# Balancing_Robot_1_2_Main.net
KiCad netlist of a schematic drawn in Altium Designer
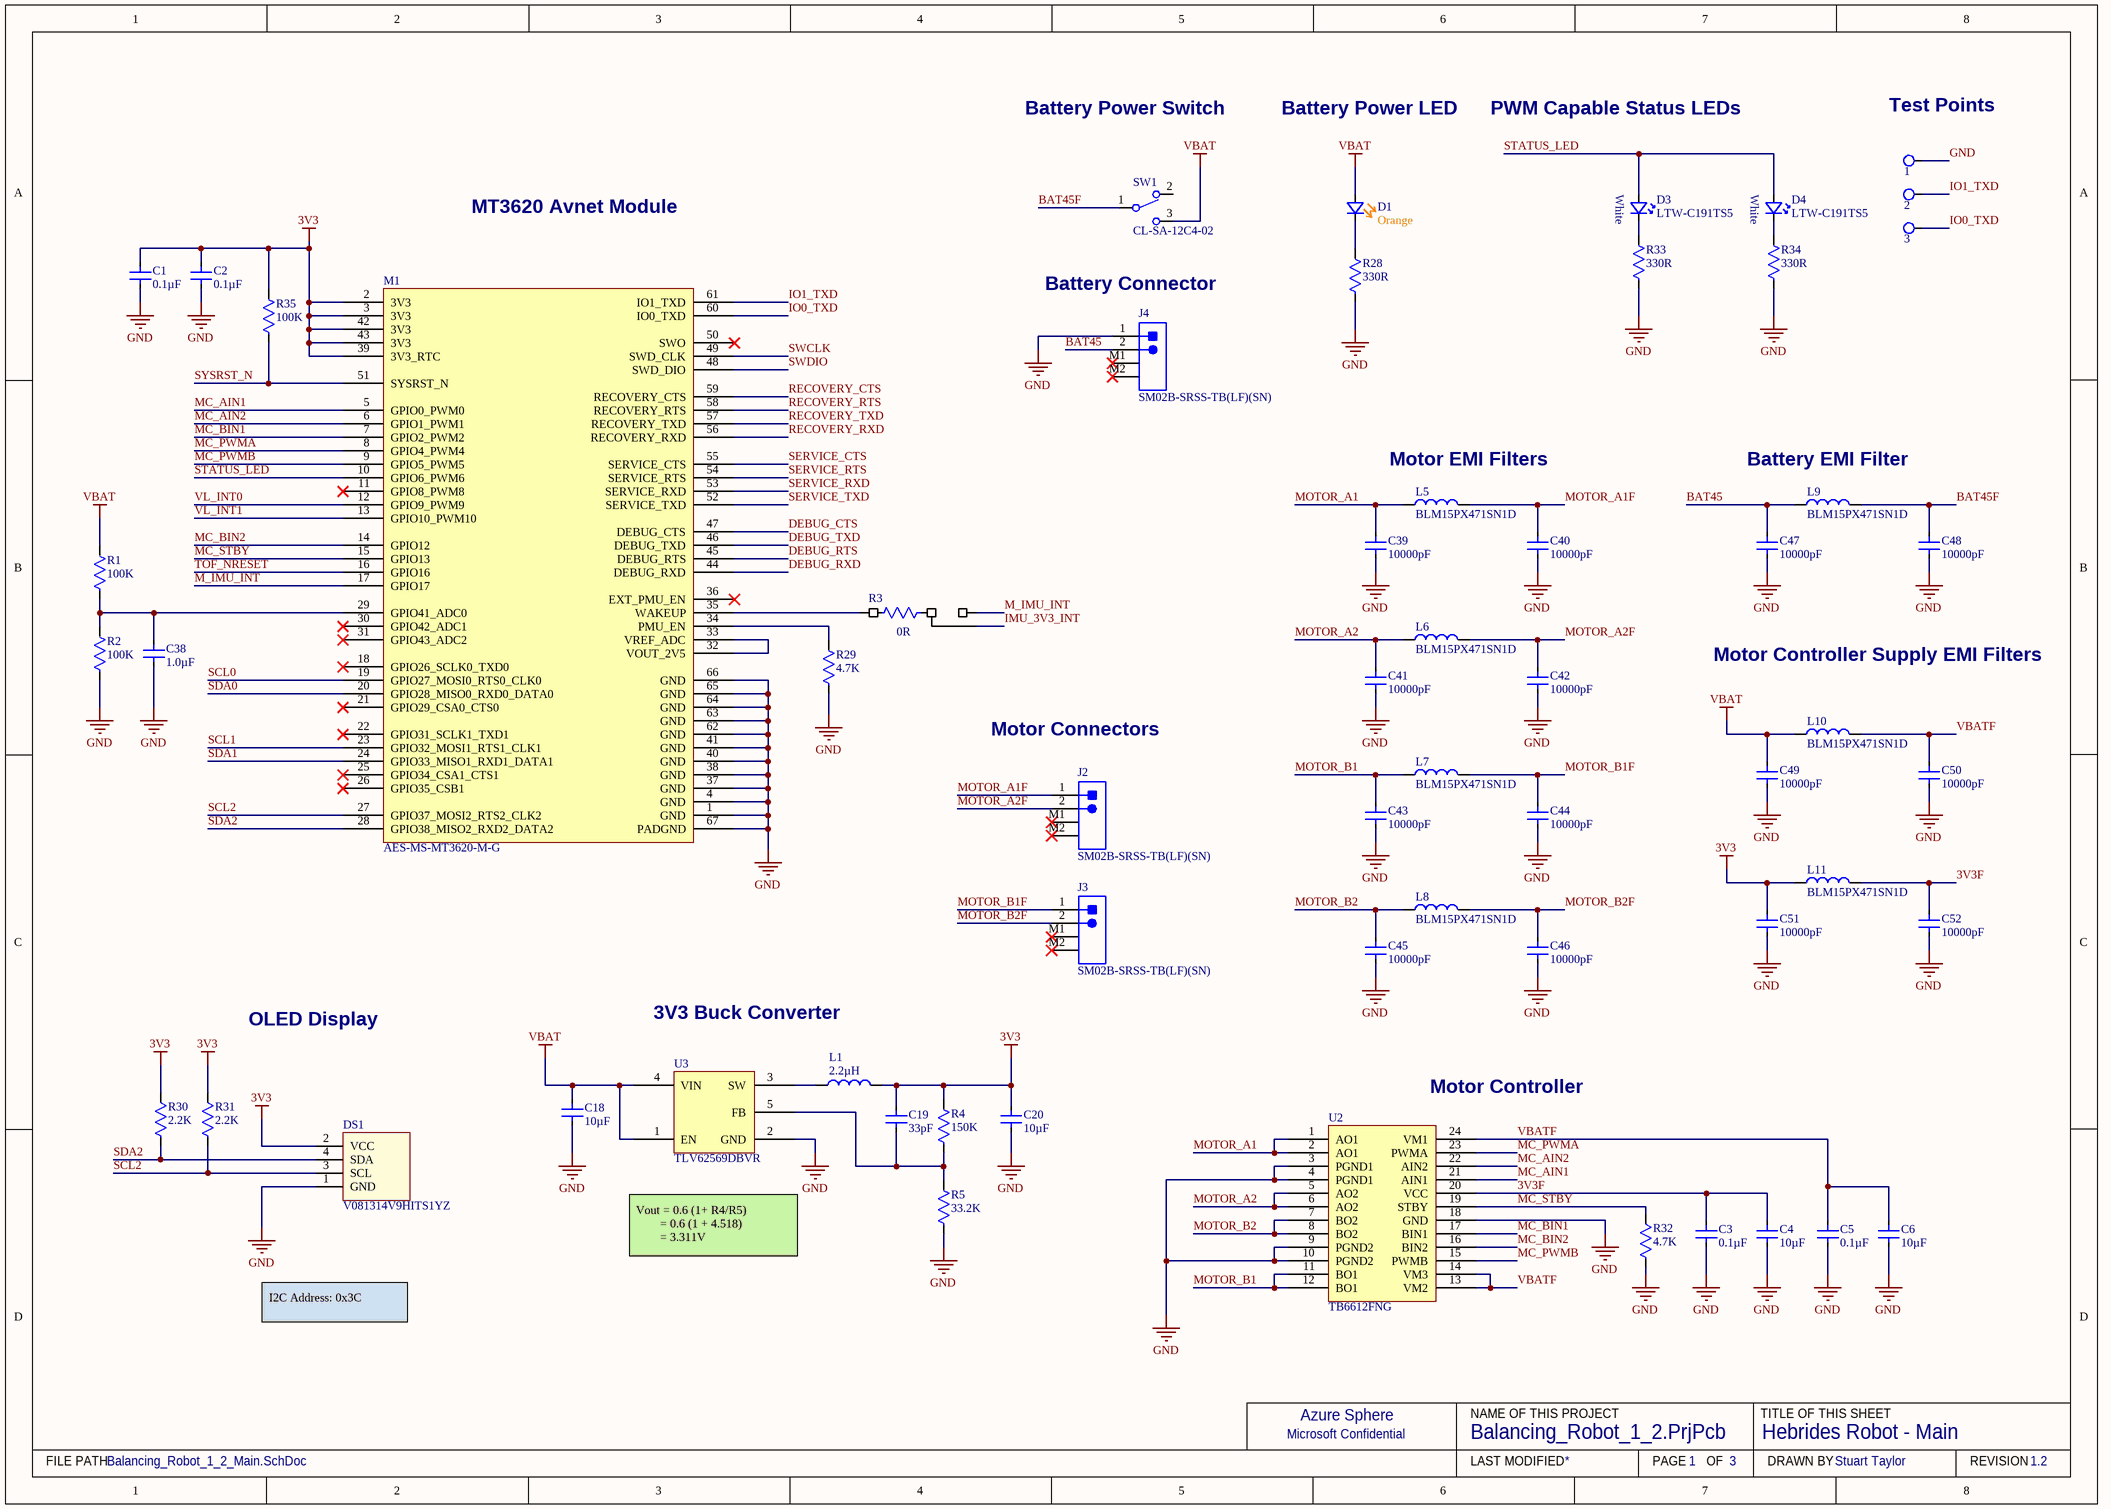
[diagram p0: Balancing_Robot_1_2_Main.SchDoc]

(export (version "E")
  (design (tool "Eeschema 10.0.6"))
  (components
    (comp (ref "1")
      (value "TestPoint")
      (footprint "Pad1.27mm")
      (description "Test Point")
      (libsource (lib "generic") (part "TestPoint"))
    )
    (comp (ref "2")
      (value "TestPoint")
      (footprint "Pad1.27mm")
      (description "Test Point")
      (libsource (lib "generic") (part "TestPoint"))
    )
    (comp (ref "3")
      (value "TestPoint")
      (footprint "Pad1.27mm")
      (description "Test Point")
      (libsource (lib "generic") (part "TestPoint"))
    )
    (comp (ref "C1")
      (value "0.1µF")
      (footprint "CAPC1005-EIA0402 0.55MM MED")
      (description "CAP CER 0.1UF 50V 10% X7R 0402")
      (fields
        (field (name "MANUFACTURER") "TDK Corporation")
        (field (name "MANUFACTURER PART NUMBER") "C1005X7R1H104K050BB")
        (field (name "CAPACITANCE") "0.1µF")
      )
      (libsource (lib "TDK_Capacitor_C_0402") (part "0.1µF 0402 X7R 50V"))
    )
    (comp (ref "C2")
      (value "0.1µF")
      (footprint "CAPC1005-EIA0402 0.55MM MED")
      (description "CAP CER 0.1UF 50V 10% X7R 0402")
      (fields
        (field (name "MANUFACTURER") "TDK Corporation")
        (field (name "MANUFACTURER PART NUMBER") "C1005X7R1H104K050BB")
        (field (name "CAPACITANCE") "0.1µF")
      )
      (libsource (lib "TDK_Capacitor_C_0402") (part "0.1µF 0402 X7R 50V"))
    )
    (comp (ref "C3")
      (value "0.1µF")
      (footprint "CAPC1005-EIA0402 0.55MM MED")
      (description "CAP CER 0.1UF 50V 10% X7R 0402")
      (fields
        (field (name "MANUFACTURER") "TDK Corporation")
        (field (name "MANUFACTURER PART NUMBER") "C1005X7R1H104K050BB")
        (field (name "CAPACITANCE") "0.1µF")
      )
      (libsource (lib "TDK_Capacitor_C_0402") (part "0.1µF 0402 X7R 50V"))
    )
    (comp (ref "C4")
      (value "10µF")
      (footprint "CAPC1005-EIA0402 0.55MM MED")
      (description "CAP CER 10UF 6.3V 20% X5R 0402")
      (fields
        (field (name "MANUFACTURER") "TDK Corporation")
        (field (name "MANUFACTURER PART NUMBER") "C1005X5R0J106M050BC")
        (field (name "CAPACITANCE") "10µF")
      )
      (libsource (lib "TDK_Capacitor_C_0402") (part "10µF 0402 X5R 6.3V"))
    )
    (comp (ref "C5")
      (value "0.1µF")
      (footprint "CAPC1005-EIA0402 0.55MM MED")
      (description "CAP CER 0.1UF 50V 10% X7R 0402")
      (fields
        (field (name "MANUFACTURER") "TDK Corporation")
        (field (name "MANUFACTURER PART NUMBER") "C1005X7R1H104K050BB")
        (field (name "CAPACITANCE") "0.1µF")
      )
      (libsource (lib "TDK_Capacitor_C_0402") (part "0.1µF 0402 X7R 50V"))
    )
    (comp (ref "C6")
      (value "10µF")
      (footprint "CAPC1005-EIA0402 0.55MM MED")
      (description "CAP CER 10UF 6.3V 20% X5R 0402")
      (fields
        (field (name "MANUFACTURER") "TDK Corporation")
        (field (name "MANUFACTURER PART NUMBER") "C1005X5R0J106M050BC")
        (field (name "CAPACITANCE") "10µF")
      )
      (libsource (lib "TDK_Capacitor_C_0402") (part "10µF 0402 X5R 6.3V"))
    )
    (comp (ref "C18")
      (value "10µF")
      (footprint "CAPC1608-EIA0603-1MM-MED")
      (description "CAP CER 10UF 25V 20% X5R 0603")
      (fields
        (field (name "MANUFACTURER") "TDK Corporation")
        (field (name "MANUFACTURER PART NUMBER") "C1608X5R1E106M080AC")
        (field (name "CAPACITANCE") "10µF")
      )
      (libsource (lib "TDK-Capacitor_C_0603") (part "10µF 0603 X5R 25V"))
    )
    (comp (ref "C19")
      (value "33pF")
      (footprint "CAPC1005-EIA0402 0.55MM MED")
      (description "CAP CER 33PF 50V 5% NP0 0402")
      (fields
        (field (name "MANUFACTURER") "TDK Corporation")
        (field (name "MANUFACTURER PART NUMBER") "C1005C0G1H330J050BA")
        (field (name "CAPACITANCE") "33pF")
      )
      (libsource (lib "TDK_Capacitor_C_0402") (part "33pF 0402 C0G, NP0 50V"))
    )
    (comp (ref "C20")
      (value "10µF")
      (footprint "CAPC1005-EIA0402 0.55MM MED")
      (description "CAP CER 10UF 6.3V 20% X5R 0402")
      (fields
        (field (name "MANUFACTURER") "TDK Corporation")
        (field (name "MANUFACTURER PART NUMBER") "C1005X5R0J106M050BC")
        (field (name "CAPACITANCE") "10µF")
      )
      (libsource (lib "TDK_Capacitor_C_0402") (part "10µF 0402 X5R 6.3V"))
    )
    (comp (ref "C38")
      (value "C1005X5R1V105K050BC")
      (footprint "CAPC1005-EIA0402 0.55MM MED")
      (description "CAP CER 1UF 35V 10% X5R 0402")
      (fields
        (field (name "MANUFACTURER") "TDK Corporation")
        (field (name "TOLERANCE") "±10%")
        (field (name "CAPACITANCE") "1.0µF")
      )
      (libsource (lib "TDK_Capacitor_C_0402") (part "1.0µF 0402 X5R 35V"))
    )
    (comp (ref "C39")
      (value "C1005X7R1H103K050BB")
      (footprint "CAPC1005-EIA0402 0.55MM MED")
      (description "CAP CER 10000PF 50V 10% X7R 0402")
      (fields
        (field (name "MANUFACTURER") "TDK Corporation")
        (field (name "TOLERANCE") "±10%")
        (field (name "CAPACITANCE") "10000pF")
      )
      (libsource (lib "TDK_Capacitor_C_0402") (part "10000pF 0402 X7R 50V"))
    )
    (comp (ref "C40")
      (value "C1005X7R1H103K050BB")
      (footprint "CAPC1005-EIA0402 0.55MM MED")
      (description "CAP CER 10000PF 50V 10% X7R 0402")
      (fields
        (field (name "MANUFACTURER") "TDK Corporation")
        (field (name "TOLERANCE") "±10%")
        (field (name "CAPACITANCE") "10000pF")
      )
      (libsource (lib "TDK_Capacitor_C_0402") (part "10000pF 0402 X7R 50V"))
    )
    (comp (ref "C41")
      (value "C1005X7R1H103K050BB")
      (footprint "CAPC1005-EIA0402 0.55MM MED")
      (description "CAP CER 10000PF 50V 10% X7R 0402")
      (fields
        (field (name "MANUFACTURER") "TDK Corporation")
        (field (name "TOLERANCE") "±10%")
        (field (name "CAPACITANCE") "10000pF")
      )
      (libsource (lib "TDK_Capacitor_C_0402") (part "10000pF 0402 X7R 50V"))
    )
    (comp (ref "C42")
      (value "C1005X7R1H103K050BB")
      (footprint "CAPC1005-EIA0402 0.55MM MED")
      (description "CAP CER 10000PF 50V 10% X7R 0402")
      (fields
        (field (name "MANUFACTURER") "TDK Corporation")
        (field (name "TOLERANCE") "±10%")
        (field (name "CAPACITANCE") "10000pF")
      )
      (libsource (lib "TDK_Capacitor_C_0402") (part "10000pF 0402 X7R 50V"))
    )
    (comp (ref "C43")
      (value "C1005X7R1H103K050BB")
      (footprint "CAPC1005-EIA0402 0.55MM MED")
      (description "CAP CER 10000PF 50V 10% X7R 0402")
      (fields
        (field (name "MANUFACTURER") "TDK Corporation")
        (field (name "TOLERANCE") "±10%")
        (field (name "CAPACITANCE") "10000pF")
      )
      (libsource (lib "TDK_Capacitor_C_0402") (part "10000pF 0402 X7R 50V"))
    )
    (comp (ref "C44")
      (value "C1005X7R1H103K050BB")
      (footprint "CAPC1005-EIA0402 0.55MM MED")
      (description "CAP CER 10000PF 50V 10% X7R 0402")
      (fields
        (field (name "MANUFACTURER") "TDK Corporation")
        (field (name "TOLERANCE") "±10%")
        (field (name "CAPACITANCE") "10000pF")
      )
      (libsource (lib "TDK_Capacitor_C_0402") (part "10000pF 0402 X7R 50V"))
    )
    (comp (ref "C45")
      (value "C1005X7R1H103K050BB")
      (footprint "CAPC1005-EIA0402 0.55MM MED")
      (description "CAP CER 10000PF 50V 10% X7R 0402")
      (fields
        (field (name "MANUFACTURER") "TDK Corporation")
        (field (name "TOLERANCE") "±10%")
        (field (name "CAPACITANCE") "10000pF")
      )
      (libsource (lib "TDK_Capacitor_C_0402") (part "10000pF 0402 X7R 50V"))
    )
    (comp (ref "C46")
      (value "C1005X7R1H103K050BB")
      (footprint "CAPC1005-EIA0402 0.55MM MED")
      (description "CAP CER 10000PF 50V 10% X7R 0402")
      (fields
        (field (name "MANUFACTURER") "TDK Corporation")
        (field (name "TOLERANCE") "±10%")
        (field (name "CAPACITANCE") "10000pF")
      )
      (libsource (lib "TDK_Capacitor_C_0402") (part "10000pF 0402 X7R 50V"))
    )
    (comp (ref "C47")
      (value "C1005X7R1H103K050BB")
      (footprint "CAPC1005-EIA0402 0.55MM MED")
      (description "CAP CER 10000PF 50V 10% X7R 0402")
      (fields
        (field (name "MANUFACTURER") "TDK Corporation")
        (field (name "TOLERANCE") "±10%")
        (field (name "CAPACITANCE") "10000pF")
      )
      (libsource (lib "TDK_Capacitor_C_0402") (part "10000pF 0402 X7R 50V"))
    )
    (comp (ref "C48")
      (value "C1005X7R1H103K050BB")
      (footprint "CAPC1005-EIA0402 0.55MM MED")
      (description "CAP CER 10000PF 50V 10% X7R 0402")
      (fields
        (field (name "MANUFACTURER") "TDK Corporation")
        (field (name "TOLERANCE") "±10%")
        (field (name "CAPACITANCE") "10000pF")
      )
      (libsource (lib "TDK_Capacitor_C_0402") (part "10000pF 0402 X7R 50V"))
    )
    (comp (ref "C49")
      (value "C1005X7R1H103K050BB")
      (footprint "CAPC1005-EIA0402 0.55MM MED")
      (description "CAP CER 10000PF 50V 10% X7R 0402")
      (fields
        (field (name "MANUFACTURER") "TDK Corporation")
        (field (name "TOLERANCE") "±10%")
        (field (name "CAPACITANCE") "10000pF")
      )
      (libsource (lib "TDK_Capacitor_C_0402") (part "10000pF 0402 X7R 50V"))
    )
    (comp (ref "C50")
      (value "C1005X7R1H103K050BB")
      (footprint "CAPC1005-EIA0402 0.55MM MED")
      (description "CAP CER 10000PF 50V 10% X7R 0402")
      (fields
        (field (name "MANUFACTURER") "TDK Corporation")
        (field (name "TOLERANCE") "±10%")
        (field (name "CAPACITANCE") "10000pF")
      )
      (libsource (lib "TDK_Capacitor_C_0402") (part "10000pF 0402 X7R 50V"))
    )
    (comp (ref "C51")
      (value "C1005X7R1H103K050BB")
      (footprint "CAPC1005-EIA0402 0.55MM MED")
      (description "CAP CER 10000PF 50V 10% X7R 0402")
      (fields
        (field (name "MANUFACTURER") "TDK Corporation")
        (field (name "TOLERANCE") "±10%")
        (field (name "CAPACITANCE") "10000pF")
      )
      (libsource (lib "TDK_Capacitor_C_0402") (part "10000pF 0402 X7R 50V"))
    )
    (comp (ref "C52")
      (value "C1005X7R1H103K050BB")
      (footprint "CAPC1005-EIA0402 0.55MM MED")
      (description "CAP CER 10000PF 50V 10% X7R 0402")
      (fields
        (field (name "MANUFACTURER") "TDK Corporation")
        (field (name "TOLERANCE") "±10%")
        (field (name "CAPACITANCE") "10000pF")
      )
      (libsource (lib "TDK_Capacitor_C_0402") (part "10000pF 0402 X7R 50V"))
    )
    (comp (ref "D1")
      (value "SML-D12D")
      (footprint "Rohm SML-D12 Orange")
      (description "1.6 x 0.8 x 0.55mm (0603) LED 605nm Orange")
      (fields
        (field (name "MANUFACTURER") "Rohm Semiconductor")
        (field (name "MANUFACTURER PART NUMBER") "SML-D12D8WT86")
        (field (name "COLOUR") "Orange")
      )
      (libsource (lib "Rohm") (part "SML-D12D"))
    )
    (comp (ref "D3")
      (value "LTW-C191TS5")
      (footprint "LTW-C191TS5")
      (description "LED Uni-Color White 2-Pin Chip LED T/R")
      (fields (field (name "MANUFACTURER") "Vishay Lite-On"))
      (libsource (lib "Lite-On") (part "LTW-C191TS5"))
    )
    (comp (ref "D4")
      (value "LTW-C191TS5")
      (footprint "LTW-C191TS5")
      (description "LED Uni-Color White 2-Pin Chip LED T/R")
      (fields (field (name "MANUFACTURER") "Vishay Lite-On"))
      (libsource (lib "Lite-On") (part "LTW-C191TS5"))
    )
    (comp (ref "DS1")
      (value "V081314V9HITS1YZ")
      (footprint "Long_Display")
      (libsource (lib "MakerHawk") (part "V081314V9HITS1YZ"))
    )
    (comp (ref "J2")
      (value "SM02B-SRSS-TB(LF)(SN)")
      (footprint "SM02B-SRSS-TB")
      (description "Conn Shrouded Header HDR 2 POS 1mm Solder RA SMD T/R")
      (fields (field (name "MANUFACTURER") "JST"))
      (libsource (lib "JST") (part "SM02B-SRSS-TB(LF)(SN)"))
    )
    (comp (ref "J3")
      (value "SM02B-SRSS-TB(LF)(SN)")
      (footprint "SM02B-SRSS-TB")
      (description "Conn Shrouded Header HDR 2 POS 1mm Solder RA SMD T/R")
      (fields (field (name "MANUFACTURER") "JST"))
      (libsource (lib "JST") (part "SM02B-SRSS-TB(LF)(SN)"))
    )
    (comp (ref "J4")
      (value "SM02B-SRSS-TB(LF)(SN)")
      (footprint "SM02B-SRSS-TB")
      (description "Conn Shrouded Header HDR 2 POS 1mm Solder RA SMD T/R")
      (fields (field (name "MANUFACTURER") "JST"))
      (libsource (lib "JST") (part "SM02B-SRSS-TB(LF)(SN)"))
    )
    (comp (ref "L1")
      (value "2.2µH")
      (footprint "NR3015T2R2M")
      (description "FIXED IND 2.2UH 1.5A 72 MOHM SMD")
      (fields
        (field (name "MANUFACTURER") "Taiyo Yuden")
        (field (name "MANUFACTURER PART NUMBER") "NR3015T2R2M")
      )
      (libsource (lib "TaiyoYuden ") (part "NR3015T2R2M"))
    )
    (comp (ref "L5")
      (value "BLM15PX471SN1D")
      (footprint "Generic Ferrite 0402")
      (description "Murata")
      (fields (field (name "TOLERANCE") "25%"))
      (libsource (lib "Murata") (part "BLM15PX471SN1D"))
    )
    (comp (ref "L6")
      (value "BLM15PX471SN1D")
      (footprint "Generic Ferrite 0402")
      (description "Murata")
      (fields (field (name "TOLERANCE") "25%"))
      (libsource (lib "Murata") (part "BLM15PX471SN1D"))
    )
    (comp (ref "L7")
      (value "BLM15PX471SN1D")
      (footprint "Generic Ferrite 0402")
      (description "Murata")
      (fields (field (name "TOLERANCE") "25%"))
      (libsource (lib "Murata") (part "BLM15PX471SN1D"))
    )
    (comp (ref "L8")
      (value "BLM15PX471SN1D")
      (footprint "Generic Ferrite 0402")
      (description "Murata")
      (fields (field (name "TOLERANCE") "25%"))
      (libsource (lib "Murata") (part "BLM15PX471SN1D"))
    )
    (comp (ref "L9")
      (value "BLM15PX471SN1D")
      (footprint "Generic Ferrite 0402")
      (description "Murata")
      (fields (field (name "TOLERANCE") "25%"))
      (libsource (lib "Murata") (part "BLM15PX471SN1D"))
    )
    (comp (ref "L10")
      (value "BLM15PX471SN1D")
      (footprint "Generic Ferrite 0402")
      (description "Murata")
      (fields (field (name "TOLERANCE") "25%"))
      (libsource (lib "Murata") (part "BLM15PX471SN1D"))
    )
    (comp (ref "L11")
      (value "BLM15PX471SN1D")
      (footprint "Generic Ferrite 0402")
      (description "Murata")
      (fields (field (name "TOLERANCE") "25%"))
      (libsource (lib "Murata") (part "BLM15PX471SN1D"))
    )
    (comp (ref "M1")
      (value "AES-MS-MT3620-M-G")
      (footprint "AES-MS-MT3620-M-G")
      (libsource (lib "Avnet") (part "AES-MS-MT3620-M-G (SAT)"))
    )
    (comp (ref "R1")
      (value "100K")
      (footprint "RES 0402 MEDIUM DENSITY")
      (description "RES 100K OHM 1/10W 1% 0402 SMD")
      (fields
        (field (name "MANUFACTURER") "Panasonic Electronic Components")
        (field (name "MANUFACTURER PART NUMBER") "ERJ-2RKF1003X")
        (field (name "RESISTANCE (OHMS)") "100K")
      )
      (libsource (lib "Panasonic_Resistor_ERJ2R") (part "100K"))
    )
    (comp (ref "R2")
      (value "100K")
      (footprint "RES 0402 MEDIUM DENSITY")
      (description "RES 100K OHM 1/10W 1% 0402 SMD")
      (fields
        (field (name "MANUFACTURER") "Panasonic Electronic Components")
        (field (name "MANUFACTURER PART NUMBER") "ERJ-2RKF1003X")
        (field (name "RESISTANCE (OHMS)") "100K")
      )
      (libsource (lib "Panasonic_Resistor_ERJ2R") (part "100K"))
    )
    (comp (ref "R3")
      (value "0R")
      (footprint "THREE-WAY-0402-NO-SHORT")
      (description "RES SMD 0.0OHM JUMPER 1/10W 0402")
      (fields
        (field (name "MANUFACTURER") "Panasonic Electronic Components")
        (field (name "MANUFACTURER PART NUMBER") "ERJ-2GE0R00X")
      )
      (libsource (lib "generic-res") (part "THREE-WAY-0R-0402-NO-SHORT"))
    )
    (comp (ref "R4")
      (value "150K")
      (footprint "RES 0402 MEDIUM DENSITY")
      (description "RES 150K OHM 1/10W 1% 0402 SMD")
      (fields
        (field (name "MANUFACTURER") "Panasonic Electronic Components")
        (field (name "MANUFACTURER PART NUMBER") "ERJ-2RKF1503X")
        (field (name "RESISTANCE (OHMS)") "150K")
      )
      (libsource (lib "Panasonic_Resistor_ERJ2R") (part "150K"))
    )
    (comp (ref "R5")
      (value "33.2K")
      (footprint "RES 0402 MEDIUM DENSITY")
      (description "RES 33.2K OHM 1/10W 1% 0402 SMD")
      (fields
        (field (name "MANUFACTURER") "Panasonic Electronic Components")
        (field (name "MANUFACTURER PART NUMBER") "ERJ-2RKF3322X")
        (field (name "RESISTANCE (OHMS)") "33.2K")
      )
      (libsource (lib "Panasonic_Resistor_ERJ2R") (part "33.2K"))
    )
    (comp (ref "R28")
      (value "330R")
      (footprint "RES 0402 MEDIUM DENSITY")
      (description "RES 330 OHM 1/10W 1% 0402 SMD")
      (fields
        (field (name "MANUFACTURER") "Panasonic Electronic Components")
        (field (name "MANUFACTURER PART NUMBER") "ERJ-2RKF3300X")
        (field (name "RESISTANCE (OHMS)") "330R")
      )
      (libsource (lib "Panasonic_Resistor_ERJ2R") (part "330R"))
    )
    (comp (ref "R29")
      (value "4.7K")
      (footprint "RES 0402 MEDIUM DENSITY")
      (description "RES 4.7K OHM 1/10W 1% 0402 SMD")
      (fields
        (field (name "MANUFACTURER") "Panasonic Electronic Components")
        (field (name "MANUFACTURER PART NUMBER") "ERJ-2RKF4701X")
        (field (name "RESISTANCE (OHMS)") "4.7K")
      )
      (libsource (lib "Panasonic_Resistor_ERJ2R") (part "4.7K"))
    )
    (comp (ref "R30")
      (value "2.2K")
      (footprint "RES 0402 MEDIUM DENSITY")
      (description "RES 2.2K OHM 1/10W 1% 0402 SMD")
      (fields
        (field (name "MANUFACTURER") "Panasonic Electronic Components")
        (field (name "MANUFACTURER PART NUMBER") "ERJ-2RKF2201X")
        (field (name "RESISTANCE (OHMS)") "2.2K")
      )
      (libsource (lib "Panasonic_Resistor_ERJ2R") (part "2.2K"))
    )
    (comp (ref "R31")
      (value "2.2K")
      (footprint "RES 0402 MEDIUM DENSITY")
      (description "RES 2.2K OHM 1/10W 1% 0402 SMD")
      (fields
        (field (name "MANUFACTURER") "Panasonic Electronic Components")
        (field (name "MANUFACTURER PART NUMBER") "ERJ-2RKF2201X")
        (field (name "RESISTANCE (OHMS)") "2.2K")
      )
      (libsource (lib "Panasonic_Resistor_ERJ2R") (part "2.2K"))
    )
    (comp (ref "R32")
      (value "4.7K")
      (footprint "RES 0402 MEDIUM DENSITY")
      (description "RES 4.7K OHM 1/10W 1% 0402 SMD")
      (fields
        (field (name "MANUFACTURER") "Panasonic Electronic Components")
        (field (name "MANUFACTURER PART NUMBER") "ERJ-2RKF4701X")
        (field (name "RESISTANCE (OHMS)") "4.7K")
      )
      (libsource (lib "Panasonic_Resistor_ERJ2R") (part "4.7K"))
    )
    (comp (ref "R33")
      (value "330R")
      (footprint "RES 0402 MEDIUM DENSITY")
      (description "RES 330 OHM 1/10W 1% 0402 SMD")
      (fields
        (field (name "MANUFACTURER") "Panasonic Electronic Components")
        (field (name "MANUFACTURER PART NUMBER") "ERJ-2RKF3300X")
        (field (name "RESISTANCE (OHMS)") "330R")
      )
      (libsource (lib "Panasonic_Resistor_ERJ2R") (part "330R"))
    )
    (comp (ref "R34")
      (value "330R")
      (footprint "RES 0402 MEDIUM DENSITY")
      (description "RES 330 OHM 1/10W 1% 0402 SMD")
      (fields
        (field (name "MANUFACTURER") "Panasonic Electronic Components")
        (field (name "MANUFACTURER PART NUMBER") "ERJ-2RKF3300X")
        (field (name "RESISTANCE (OHMS)") "330R")
      )
      (libsource (lib "Panasonic_Resistor_ERJ2R") (part "330R"))
    )
    (comp (ref "R35")
      (value "100K")
      (footprint "RES 0402 MEDIUM DENSITY")
      (description "RES 100K OHM 1/10W 1% 0402 SMD")
      (fields
        (field (name "MANUFACTURER") "Panasonic Electronic Components")
        (field (name "MANUFACTURER PART NUMBER") "ERJ-2RKF1003X")
        (field (name "RESISTANCE (OHMS)") "100K")
      )
      (libsource (lib "Panasonic_Resistor_ERJ2R") (part "100K"))
    )
    (comp (ref "SW1")
      (value "CL-SA-12C4-02")
      (footprint "CL-SA-12C4-02")
      (description "SWITCH SLIDE SPDT 500MA 12V")
      (fields (field (name "MANUFACTURER") "Nidec Copal"))
      (libsource (lib "Copal") (part "CL-SA-12C4-02"))
    )
    (comp (ref "U2")
      (value "TB6612FNG")
      (footprint "TB6612FNG")
      (description "DC Motor Driver 3V 24-Pin SSOP T/R")
      (fields
        (field (name "MANUFACTURER") "Toshiba")
        (field (name "MANUFACTURER PART NUMBER") "TB6612FNG,C,8,EL")
      )
      (libsource (lib "Toshiba") (part "TB6612FNG"))
    )
    (comp (ref "U3")
      (value "TLV62569DBVR")
      (footprint "TI-SOT23-6")
      (description "Variable voltage buck converter")
      (fields (field (name "MANUFACTURER") "Texas Instruments"))
      (libsource (lib "TexasInstruments") (part "TLV62569DBVR"))
    )
  )
  (nets
    (net (code "1") (name "/3V3F") (class "Default")
      (node (ref "C3") (pin "2") (pinfunction "2_2") (pintype "passive"))
      (node (ref "C4") (pin "2") (pinfunction "2_2") (pintype "passive"))
      (node (ref "C52") (pin "2") (pinfunction "2_2") (pintype "passive"))
      (node (ref "L11") (pin "2") (pinfunction "2_2") (pintype "passive"))
      (node (ref "U2") (pin "20") (pinfunction "VCC_20") (pintype "passive"))
    )
    (net (code "2") (name "/BAT45") (class "Default")
      (node (ref "C47") (pin "2") (pinfunction "2_2") (pintype "passive"))
      (node (ref "J4") (pin "2") (pinfunction "2_2") (pintype "passive"))
      (node (ref "L9") (pin "1") (pinfunction "1_1") (pintype "passive"))
    )
    (net (code "3") (name "/BAT45F") (class "Default")
      (node (ref "C48") (pin "2") (pinfunction "2_2") (pintype "passive"))
      (node (ref "L9") (pin "2") (pinfunction "2_2") (pintype "passive"))
      (node (ref "SW1") (pin "1") (pinfunction "1_1") (pintype "passive"))
    )
    (net (code "4") (name "/DEBUG_CTS") (class "Default")
      (node (ref "M1") (pin "47") (pinfunction "DEBUG_CTS_47") (pintype "passive"))
    )
    (net (code "5") (name "/DEBUG_RTS") (class "Default")
      (node (ref "M1") (pin "45") (pinfunction "DEBUG_RTS_45") (pintype "passive"))
    )
    (net (code "6") (name "/DEBUG_RXD") (class "Default")
      (node (ref "M1") (pin "44") (pinfunction "DEBUG_RXD_44") (pintype "passive"))
    )
    (net (code "7") (name "/DEBUG_TXD") (class "Default")
      (node (ref "M1") (pin "46") (pinfunction "DEBUG_TXD_46") (pintype "passive"))
    )
    (net (code "8") (name "/IMU_3V3_INT") (class "Default")
      (node (ref "R3") (pin "2") (pinfunction "2_2") (pintype "passive"))
    )
    (net (code "9") (name "/IO0_TXD") (class "Default")
      (node (ref "3") (pin "1") (pinfunction "1_1") (pintype "passive"))
      (node (ref "M1") (pin "60") (pinfunction "IO0_TXD_60") (pintype "passive"))
    )
    (net (code "10") (name "/IO1_TXD") (class "Default")
      (node (ref "2") (pin "1") (pinfunction "1_1") (pintype "passive"))
      (node (ref "M1") (pin "61") (pinfunction "IO1_TXD_61") (pintype "passive"))
    )
    (net (code "11") (name "/MC_AIN1") (class "Default")
      (node (ref "M1") (pin "5") (pinfunction "GPIO0_PWM0_5") (pintype "passive"))
      (node (ref "U2") (pin "21") (pinfunction "AIN1_21") (pintype "passive"))
    )
    (net (code "12") (name "/MC_AIN2") (class "Default")
      (node (ref "M1") (pin "6") (pinfunction "GPIO1_PWM1_6") (pintype "passive"))
      (node (ref "U2") (pin "22") (pinfunction "AIN2_22") (pintype "passive"))
    )
    (net (code "13") (name "/MC_BIN1") (class "Default")
      (node (ref "M1") (pin "7") (pinfunction "GPIO2_PWM2_7") (pintype "passive"))
      (node (ref "U2") (pin "17") (pinfunction "BIN1_17") (pintype "passive"))
    )
    (net (code "14") (name "/MC_BIN2") (class "Default")
      (node (ref "M1") (pin "14") (pinfunction "GPIO12_14") (pintype "passive"))
      (node (ref "U2") (pin "16") (pinfunction "BIN2_16") (pintype "passive"))
    )
    (net (code "15") (name "/MC_PWMA") (class "Default")
      (node (ref "M1") (pin "8") (pinfunction "GPIO4_PWM4_8") (pintype "passive"))
      (node (ref "U2") (pin "23") (pinfunction "PWMA_23") (pintype "passive"))
    )
    (net (code "16") (name "/MC_PWMB") (class "Default")
      (node (ref "M1") (pin "9") (pinfunction "GPIO5_PWM5_9") (pintype "passive"))
      (node (ref "U2") (pin "15") (pinfunction "PWMB_15") (pintype "passive"))
    )
    (net (code "17") (name "/MC_STBY") (class "Default")
      (node (ref "M1") (pin "15") (pinfunction "GPIO13_15") (pintype "passive"))
      (node (ref "R32") (pin "1") (pinfunction "1_1") (pintype "passive"))
      (node (ref "U2") (pin "19") (pinfunction "STBY_19") (pintype "passive"))
    )
    (net (code "18") (name "/MOTOR_A1") (class "Default")
      (node (ref "C39") (pin "2") (pinfunction "2_2") (pintype "passive"))
      (node (ref "L5") (pin "1") (pinfunction "1_1") (pintype "passive"))
      (node (ref "U2") (pin "1") (pinfunction "AO1_1") (pintype "passive"))
      (node (ref "U2") (pin "2") (pinfunction "AO1_2") (pintype "passive"))
    )
    (net (code "19") (name "/MOTOR_A1F") (class "Default")
      (node (ref "C40") (pin "2") (pinfunction "2_2") (pintype "passive"))
      (node (ref "J2") (pin "1") (pinfunction "1_1") (pintype "passive"))
      (node (ref "L5") (pin "2") (pinfunction "2_2") (pintype "passive"))
    )
    (net (code "20") (name "/MOTOR_A2") (class "Default")
      (node (ref "C41") (pin "2") (pinfunction "2_2") (pintype "passive"))
      (node (ref "L6") (pin "1") (pinfunction "1_1") (pintype "passive"))
      (node (ref "U2") (pin "5") (pinfunction "AO2_5") (pintype "passive"))
      (node (ref "U2") (pin "6") (pinfunction "AO2_6") (pintype "passive"))
    )
    (net (code "21") (name "/MOTOR_A2F") (class "Default")
      (node (ref "C42") (pin "2") (pinfunction "2_2") (pintype "passive"))
      (node (ref "J2") (pin "2") (pinfunction "2_2") (pintype "passive"))
      (node (ref "L6") (pin "2") (pinfunction "2_2") (pintype "passive"))
    )
    (net (code "22") (name "/MOTOR_B1") (class "Default")
      (node (ref "C43") (pin "2") (pinfunction "2_2") (pintype "passive"))
      (node (ref "L7") (pin "1") (pinfunction "1_1") (pintype "passive"))
      (node (ref "U2") (pin "11") (pinfunction "BO1_11") (pintype "passive"))
      (node (ref "U2") (pin "12") (pinfunction "BO1_12") (pintype "passive"))
    )
    (net (code "23") (name "/MOTOR_B1F") (class "Default")
      (node (ref "C44") (pin "2") (pinfunction "2_2") (pintype "passive"))
      (node (ref "J3") (pin "1") (pinfunction "1_1") (pintype "passive"))
      (node (ref "L7") (pin "2") (pinfunction "2_2") (pintype "passive"))
    )
    (net (code "24") (name "/MOTOR_B2") (class "Default")
      (node (ref "C45") (pin "2") (pinfunction "2_2") (pintype "passive"))
      (node (ref "L8") (pin "1") (pinfunction "1_1") (pintype "passive"))
      (node (ref "U2") (pin "7") (pinfunction "BO2_7") (pintype "passive"))
      (node (ref "U2") (pin "8") (pinfunction "BO2_8") (pintype "passive"))
    )
    (net (code "25") (name "/MOTOR_B2F") (class "Default")
      (node (ref "C46") (pin "2") (pinfunction "2_2") (pintype "passive"))
      (node (ref "J3") (pin "2") (pinfunction "2_2") (pintype "passive"))
      (node (ref "L8") (pin "2") (pinfunction "2_2") (pintype "passive"))
    )
    (net (code "26") (name "/M_IMU_INT") (class "Default")
      (node (ref "M1") (pin "17") (pinfunction "GPIO17_17") (pintype "passive"))
      (node (ref "R3") (pin "3") (pinfunction "3_3") (pintype "passive"))
    )
    (net (code "27") (name "/RECOVERY_CTS") (class "Default")
      (node (ref "M1") (pin "59") (pinfunction "RECOVERY_CTS_59") (pintype "passive"))
    )
    (net (code "28") (name "/RECOVERY_RTS") (class "Default")
      (node (ref "M1") (pin "58") (pinfunction "RECOVERY_RTS_58") (pintype "passive"))
    )
    (net (code "29") (name "/RECOVERY_RXD") (class "Default")
      (node (ref "M1") (pin "56") (pinfunction "RECOVERY_RXD_56") (pintype "passive"))
    )
    (net (code "30") (name "/RECOVERY_TXD") (class "Default")
      (node (ref "M1") (pin "57") (pinfunction "RECOVERY_TXD_57") (pintype "passive"))
    )
    (net (code "31") (name "/SCL0") (class "Default")
      (node (ref "M1") (pin "19") (pinfunction "GPIO27_MOSI0_RTS0_CLK0_19") (pintype "passive"))
    )
    (net (code "32") (name "/SCL1") (class "Default")
      (node (ref "M1") (pin "23") (pinfunction "GPIO32_MOSI1_RTS1_CLK1_23") (pintype "passive"))
    )
    (net (code "33") (name "/SCL2") (class "Default")
      (node (ref "DS1") (pin "3") (pinfunction "SCL_3") (pintype "passive"))
      (node (ref "M1") (pin "27") (pinfunction "GPIO37_MOSI2_RTS2_CLK2_27") (pintype "passive"))
      (node (ref "R31") (pin "2") (pinfunction "2_2") (pintype "passive"))
    )
    (net (code "34") (name "/SDA0") (class "Default")
      (node (ref "M1") (pin "20") (pinfunction "GPIO28_MISO0_RXD0_DATA0_20") (pintype "passive"))
    )
    (net (code "35") (name "/SDA1") (class "Default")
      (node (ref "M1") (pin "24") (pinfunction "GPIO33_MISO1_RXD1_DATA1_24") (pintype "passive"))
    )
    (net (code "36") (name "/SDA2") (class "Default")
      (node (ref "DS1") (pin "4") (pinfunction "SDA_4") (pintype "passive"))
      (node (ref "M1") (pin "28") (pinfunction "GPIO38_MISO2_RXD2_DATA2_28") (pintype "passive"))
      (node (ref "R30") (pin "2") (pinfunction "2_2") (pintype "passive"))
    )
    (net (code "37") (name "/SERVICE_CTS") (class "Default")
      (node (ref "M1") (pin "55") (pinfunction "SERVICE_CTS_55") (pintype "passive"))
    )
    (net (code "38") (name "/SERVICE_RTS") (class "Default")
      (node (ref "M1") (pin "54") (pinfunction "SERVICE_RTS_54") (pintype "passive"))
    )
    (net (code "39") (name "/SERVICE_RXD") (class "Default")
      (node (ref "M1") (pin "53") (pinfunction "SERVICE_RXD_53") (pintype "passive"))
    )
    (net (code "40") (name "/SERVICE_TXD") (class "Default")
      (node (ref "M1") (pin "52") (pinfunction "SERVICE_TXD_52") (pintype "passive"))
    )
    (net (code "41") (name "/STATUS_LED") (class "Default")
      (node (ref "D3") (pin "2") (pinfunction "A_2") (pintype "passive"))
      (node (ref "D4") (pin "2") (pinfunction "A_2") (pintype "passive"))
      (node (ref "M1") (pin "10") (pinfunction "GPIO6_PWM6_10") (pintype "passive"))
    )
    (net (code "42") (name "/SWCLK") (class "Default")
      (node (ref "M1") (pin "49") (pinfunction "SWD_CLK_49") (pintype "passive"))
    )
    (net (code "43") (name "/SWDIO") (class "Default")
      (node (ref "M1") (pin "48") (pinfunction "SWD_DIO_48") (pintype "passive"))
    )
    (net (code "44") (name "/SYSRST_N") (class "Default")
      (node (ref "M1") (pin "51") (pinfunction "SYSRST_N_51") (pintype "passive"))
      (node (ref "R35") (pin "2") (pinfunction "2_2") (pintype "passive"))
    )
    (net (code "45") (name "/TOF_NRESET") (class "Default")
      (node (ref "M1") (pin "16") (pinfunction "GPIO16_16") (pintype "passive"))
    )
    (net (code "46") (name "/VBATF") (class "Default")
      (node (ref "C5") (pin "2") (pinfunction "2_2") (pintype "passive"))
      (node (ref "C50") (pin "2") (pinfunction "2_2") (pintype "passive"))
      (node (ref "C6") (pin "2") (pinfunction "2_2") (pintype "passive"))
      (node (ref "L10") (pin "2") (pinfunction "2_2") (pintype "passive"))
      (node (ref "U2") (pin "13") (pinfunction "VM2_13") (pintype "passive"))
      (node (ref "U2") (pin "14") (pinfunction "VM3_14") (pintype "passive"))
      (node (ref "U2") (pin "24") (pinfunction "VM1_24") (pintype "passive"))
    )
    (net (code "47") (name "/VL_INT0") (class "Default")
      (node (ref "M1") (pin "12") (pinfunction "GPIO9_PWM9_12") (pintype "passive"))
    )
    (net (code "48") (name "/VL_INT1") (class "Default")
      (node (ref "M1") (pin "13") (pinfunction "GPIO10_PWM10_13") (pintype "passive"))
    )
    (net (code "49") (name "3V3") (class "Default")
      (node (ref "C1") (pin "2") (pinfunction "2_2") (pintype "passive"))
      (node (ref "C19") (pin "2") (pinfunction "2_2") (pintype "passive"))
      (node (ref "C2") (pin "2") (pinfunction "2_2") (pintype "passive"))
      (node (ref "C20") (pin "2") (pinfunction "2_2") (pintype "passive"))
      (node (ref "C51") (pin "2") (pinfunction "2_2") (pintype "passive"))
      (node (ref "DS1") (pin "2") (pinfunction "VCC_2") (pintype "passive"))
      (node (ref "L1") (pin "2") (pinfunction "2_2") (pintype "passive"))
      (node (ref "L11") (pin "1") (pinfunction "1_1") (pintype "passive"))
      (node (ref "M1") (pin "2") (pinfunction "3V3_2") (pintype "passive"))
      (node (ref "M1") (pin "3") (pinfunction "3V3_3") (pintype "passive"))
      (node (ref "M1") (pin "39") (pinfunction "3V3_RTC_39") (pintype "passive"))
      (node (ref "M1") (pin "42") (pinfunction "3V3_42") (pintype "passive"))
      (node (ref "M1") (pin "43") (pinfunction "3V3_43") (pintype "passive"))
      (node (ref "R30") (pin "1") (pinfunction "1_1") (pintype "passive"))
      (node (ref "R31") (pin "1") (pinfunction "1_1") (pintype "passive"))
      (node (ref "R35") (pin "1") (pinfunction "1_1") (pintype "passive"))
      (node (ref "R4") (pin "1") (pinfunction "1_1") (pintype "passive"))
    )
    (net (code "50") (name "GND") (class "Default")
      (node (ref "1") (pin "1") (pinfunction "1_1") (pintype "passive"))
      (node (ref "C1") (pin "1") (pinfunction "1_1") (pintype "passive"))
      (node (ref "C18") (pin "1") (pinfunction "1_1") (pintype "passive"))
      (node (ref "C2") (pin "1") (pinfunction "1_1") (pintype "passive"))
      (node (ref "C20") (pin "1") (pinfunction "1_1") (pintype "passive"))
      (node (ref "C3") (pin "1") (pinfunction "1_1") (pintype "passive"))
      (node (ref "C38") (pin "1") (pinfunction "1_1") (pintype "passive"))
      (node (ref "C39") (pin "1") (pinfunction "1_1") (pintype "passive"))
      (node (ref "C4") (pin "1") (pinfunction "1_1") (pintype "passive"))
      (node (ref "C40") (pin "1") (pinfunction "1_1") (pintype "passive"))
      (node (ref "C41") (pin "1") (pinfunction "1_1") (pintype "passive"))
      (node (ref "C42") (pin "1") (pinfunction "1_1") (pintype "passive"))
      (node (ref "C43") (pin "1") (pinfunction "1_1") (pintype "passive"))
      (node (ref "C44") (pin "1") (pinfunction "1_1") (pintype "passive"))
      (node (ref "C45") (pin "1") (pinfunction "1_1") (pintype "passive"))
      (node (ref "C46") (pin "1") (pinfunction "1_1") (pintype "passive"))
      (node (ref "C47") (pin "1") (pinfunction "1_1") (pintype "passive"))
      (node (ref "C48") (pin "1") (pinfunction "1_1") (pintype "passive"))
      (node (ref "C49") (pin "1") (pinfunction "1_1") (pintype "passive"))
      (node (ref "C5") (pin "1") (pinfunction "1_1") (pintype "passive"))
      (node (ref "C50") (pin "1") (pinfunction "1_1") (pintype "passive"))
      (node (ref "C51") (pin "1") (pinfunction "1_1") (pintype "passive"))
      (node (ref "C52") (pin "1") (pinfunction "1_1") (pintype "passive"))
      (node (ref "C6") (pin "1") (pinfunction "1_1") (pintype "passive"))
      (node (ref "DS1") (pin "1") (pinfunction "GND_1") (pintype "passive"))
      (node (ref "J4") (pin "1") (pinfunction "1_1") (pintype "passive"))
      (node (ref "M1") (pin "1") (pinfunction "GND_1") (pintype "passive"))
      (node (ref "M1") (pin "37") (pinfunction "GND_37") (pintype "passive"))
      (node (ref "M1") (pin "38") (pinfunction "GND_38") (pintype "passive"))
      (node (ref "M1") (pin "4") (pinfunction "GND_4") (pintype "passive"))
      (node (ref "M1") (pin "40") (pinfunction "GND_40") (pintype "passive"))
      (node (ref "M1") (pin "41") (pinfunction "GND_41") (pintype "passive"))
      (node (ref "M1") (pin "62") (pinfunction "GND_62") (pintype "passive"))
      (node (ref "M1") (pin "63") (pinfunction "GND_63") (pintype "passive"))
      (node (ref "M1") (pin "64") (pinfunction "GND_64") (pintype "passive"))
      (node (ref "M1") (pin "65") (pinfunction "GND_65") (pintype "passive"))
      (node (ref "M1") (pin "66") (pinfunction "GND_66") (pintype "passive"))
      (node (ref "M1") (pin "67") (pinfunction "PADGND_67") (pintype "passive"))
      (node (ref "R2") (pin "2") (pinfunction "2_2") (pintype "passive"))
      (node (ref "R28") (pin "2") (pinfunction "2_2") (pintype "passive"))
      (node (ref "R29") (pin "2") (pinfunction "2_2") (pintype "passive"))
      (node (ref "R32") (pin "2") (pinfunction "2_2") (pintype "passive"))
      (node (ref "R33") (pin "2") (pinfunction "2_2") (pintype "passive"))
      (node (ref "R34") (pin "2") (pinfunction "2_2") (pintype "passive"))
      (node (ref "R5") (pin "2") (pinfunction "2_2") (pintype "passive"))
      (node (ref "U2") (pin "10") (pinfunction "PGND2_10") (pintype "passive"))
      (node (ref "U2") (pin "18") (pinfunction "GND_18") (pintype "passive"))
      (node (ref "U2") (pin "3") (pinfunction "PGND1_3") (pintype "passive"))
      (node (ref "U2") (pin "4") (pinfunction "PGND1_4") (pintype "passive"))
      (node (ref "U2") (pin "9") (pinfunction "PGND2_9") (pintype "passive"))
      (node (ref "U3") (pin "2") (pinfunction "GND_2") (pintype "passive"))
    )
    (net (code "51") (name "Net-(D1-K)") (class "Default")
      (node (ref "D1") (pin "1") (pinfunction "K_1") (pintype "passive"))
      (node (ref "R28") (pin "1") (pinfunction "1_1") (pintype "passive"))
    )
    (net (code "52") (name "Net-(D3-K)") (class "Default")
      (node (ref "D3") (pin "1") (pinfunction "K_1") (pintype "passive"))
      (node (ref "R33") (pin "1") (pinfunction "1_1") (pintype "passive"))
    )
    (net (code "53") (name "Net-(D4-K)") (class "Default")
      (node (ref "D4") (pin "1") (pinfunction "K_1") (pintype "passive"))
      (node (ref "R34") (pin "1") (pinfunction "1_1") (pintype "passive"))
    )
    (net (code "54") (name "Net-(M1-GPIO41_ADC0)") (class "Default")
      (node (ref "C38") (pin "2") (pinfunction "2_2") (pintype "passive"))
      (node (ref "M1") (pin "29") (pinfunction "GPIO41_ADC0_29") (pintype "passive"))
      (node (ref "R1") (pin "2") (pinfunction "2_2") (pintype "passive"))
      (node (ref "R2") (pin "1") (pinfunction "1_1") (pintype "passive"))
    )
    (net (code "55") (name "Net-(M1-PMU_EN)") (class "Default")
      (node (ref "M1") (pin "34") (pinfunction "PMU_EN_34") (pintype "passive"))
      (node (ref "R29") (pin "1") (pinfunction "1_1") (pintype "passive"))
    )
    (net (code "56") (name "Net-(M1-VOUT_2V5)") (class "Default")
      (node (ref "M1") (pin "32") (pinfunction "VOUT_2V5_32") (pintype "passive"))
      (node (ref "M1") (pin "33") (pinfunction "VREF_ADC_33") (pintype "passive"))
    )
    (net (code "57") (name "Net-(M1-WAKEUP)") (class "Default")
      (node (ref "M1") (pin "35") (pinfunction "WAKEUP_35") (pintype "passive"))
      (node (ref "R3") (pin "1") (pinfunction "1_1") (pintype "passive"))
    )
    (net (code "58") (name "Net-(U3-FB)") (class "Default")
      (node (ref "C19") (pin "1") (pinfunction "1_1") (pintype "passive"))
      (node (ref "R4") (pin "2") (pinfunction "2_2") (pintype "passive"))
      (node (ref "R5") (pin "1") (pinfunction "1_1") (pintype "passive"))
      (node (ref "U3") (pin "5") (pinfunction "FB_5") (pintype "passive"))
    )
    (net (code "59") (name "Net-(U3-SW)") (class "Default")
      (node (ref "L1") (pin "1") (pinfunction "1_1") (pintype "passive"))
      (node (ref "U3") (pin "3") (pinfunction "SW_3") (pintype "passive"))
    )
    (net (code "60") (name "VBAT") (class "Default")
      (node (ref "C18") (pin "2") (pinfunction "2_2") (pintype "passive"))
      (node (ref "C49") (pin "2") (pinfunction "2_2") (pintype "passive"))
      (node (ref "D1") (pin "2") (pinfunction "A_2") (pintype "passive"))
      (node (ref "L10") (pin "1") (pinfunction "1_1") (pintype "passive"))
      (node (ref "R1") (pin "1") (pinfunction "1_1") (pintype "passive"))
      (node (ref "SW1") (pin "3") (pinfunction "3_3") (pintype "passive"))
      (node (ref "U3") (pin "1") (pinfunction "EN_1") (pintype "passive"))
      (node (ref "U3") (pin "4") (pinfunction "VIN_4") (pintype "passive"))
    )
    (net (code "61") (name "unconnected-(J2-PadM1)") (class "Default")
      (node (ref "J2") (pin "M1") (pinfunction "M1_M1") (pintype "passive+no_connect"))
    )
    (net (code "62") (name "unconnected-(J2-PadM2)") (class "Default")
      (node (ref "J2") (pin "M2") (pinfunction "M2_M2") (pintype "passive+no_connect"))
    )
    (net (code "63") (name "unconnected-(J3-PadM1)") (class "Default")
      (node (ref "J3") (pin "M1") (pinfunction "M1_M1") (pintype "passive+no_connect"))
    )
    (net (code "64") (name "unconnected-(J3-PadM2)") (class "Default")
      (node (ref "J3") (pin "M2") (pinfunction "M2_M2") (pintype "passive+no_connect"))
    )
    (net (code "65") (name "unconnected-(J4-PadM1)") (class "Default")
      (node (ref "J4") (pin "M1") (pinfunction "M1_M1") (pintype "passive+no_connect"))
    )
    (net (code "66") (name "unconnected-(J4-PadM2)") (class "Default")
      (node (ref "J4") (pin "M2") (pinfunction "M2_M2") (pintype "passive+no_connect"))
    )
    (net (code "67") (name "unconnected-(M1-EXT_PMU_EN-Pad36)") (class "Default")
      (node (ref "M1") (pin "36") (pinfunction "EXT_PMU_EN_36") (pintype "passive+no_connect"))
    )
    (net (code "68") (name "unconnected-(M1-GPIO8_PWM8-Pad11)") (class "Default")
      (node (ref "M1") (pin "11") (pinfunction "GPIO8_PWM8_11") (pintype "passive+no_connect"))
    )
    (net (code "69") (name "unconnected-(M1-GPIO26_SCLK0_TXD0-Pad18)") (class "Default")
      (node (ref "M1") (pin "18") (pinfunction "GPIO26_SCLK0_TXD0_18") (pintype "passive+no_connect"))
    )
    (net (code "70") (name "unconnected-(M1-GPIO29_CSA0_CTS0-Pad21)") (class "Default")
      (node (ref "M1") (pin "21") (pinfunction "GPIO29_CSA0_CTS0_21") (pintype "passive+no_connect"))
    )
    (net (code "71") (name "unconnected-(M1-GPIO31_SCLK1_TXD1-Pad22)") (class "Default")
      (node (ref "M1") (pin "22") (pinfunction "GPIO31_SCLK1_TXD1_22") (pintype "passive+no_connect"))
    )
    (net (code "72") (name "unconnected-(M1-GPIO34_CSA1_CTS1-Pad25)") (class "Default")
      (node (ref "M1") (pin "25") (pinfunction "GPIO34_CSA1_CTS1_25") (pintype "passive+no_connect"))
    )
    (net (code "73") (name "unconnected-(M1-GPIO35_CSB1-Pad26)") (class "Default")
      (node (ref "M1") (pin "26") (pinfunction "GPIO35_CSB1_26") (pintype "passive+no_connect"))
    )
    (net (code "74") (name "unconnected-(M1-GPIO42_ADC1-Pad30)") (class "Default")
      (node (ref "M1") (pin "30") (pinfunction "GPIO42_ADC1_30") (pintype "passive+no_connect"))
    )
    (net (code "75") (name "unconnected-(M1-GPIO43_ADC2-Pad31)") (class "Default")
      (node (ref "M1") (pin "31") (pinfunction "GPIO43_ADC2_31") (pintype "passive+no_connect"))
    )
    (net (code "76") (name "unconnected-(M1-SWO-Pad50)") (class "Default")
      (node (ref "M1") (pin "50") (pinfunction "SWO_50") (pintype "passive+no_connect"))
    )
    (net (code "77") (name "unconnected-(SW1-Pad2)") (class "Default")
      (node (ref "SW1") (pin "2") (pinfunction "2_2") (pintype "passive"))
    )
  )
)
